# SuperCap-NEW_V2_1_2.net
KiCad netlist of a schematic drawn in Altium Designer
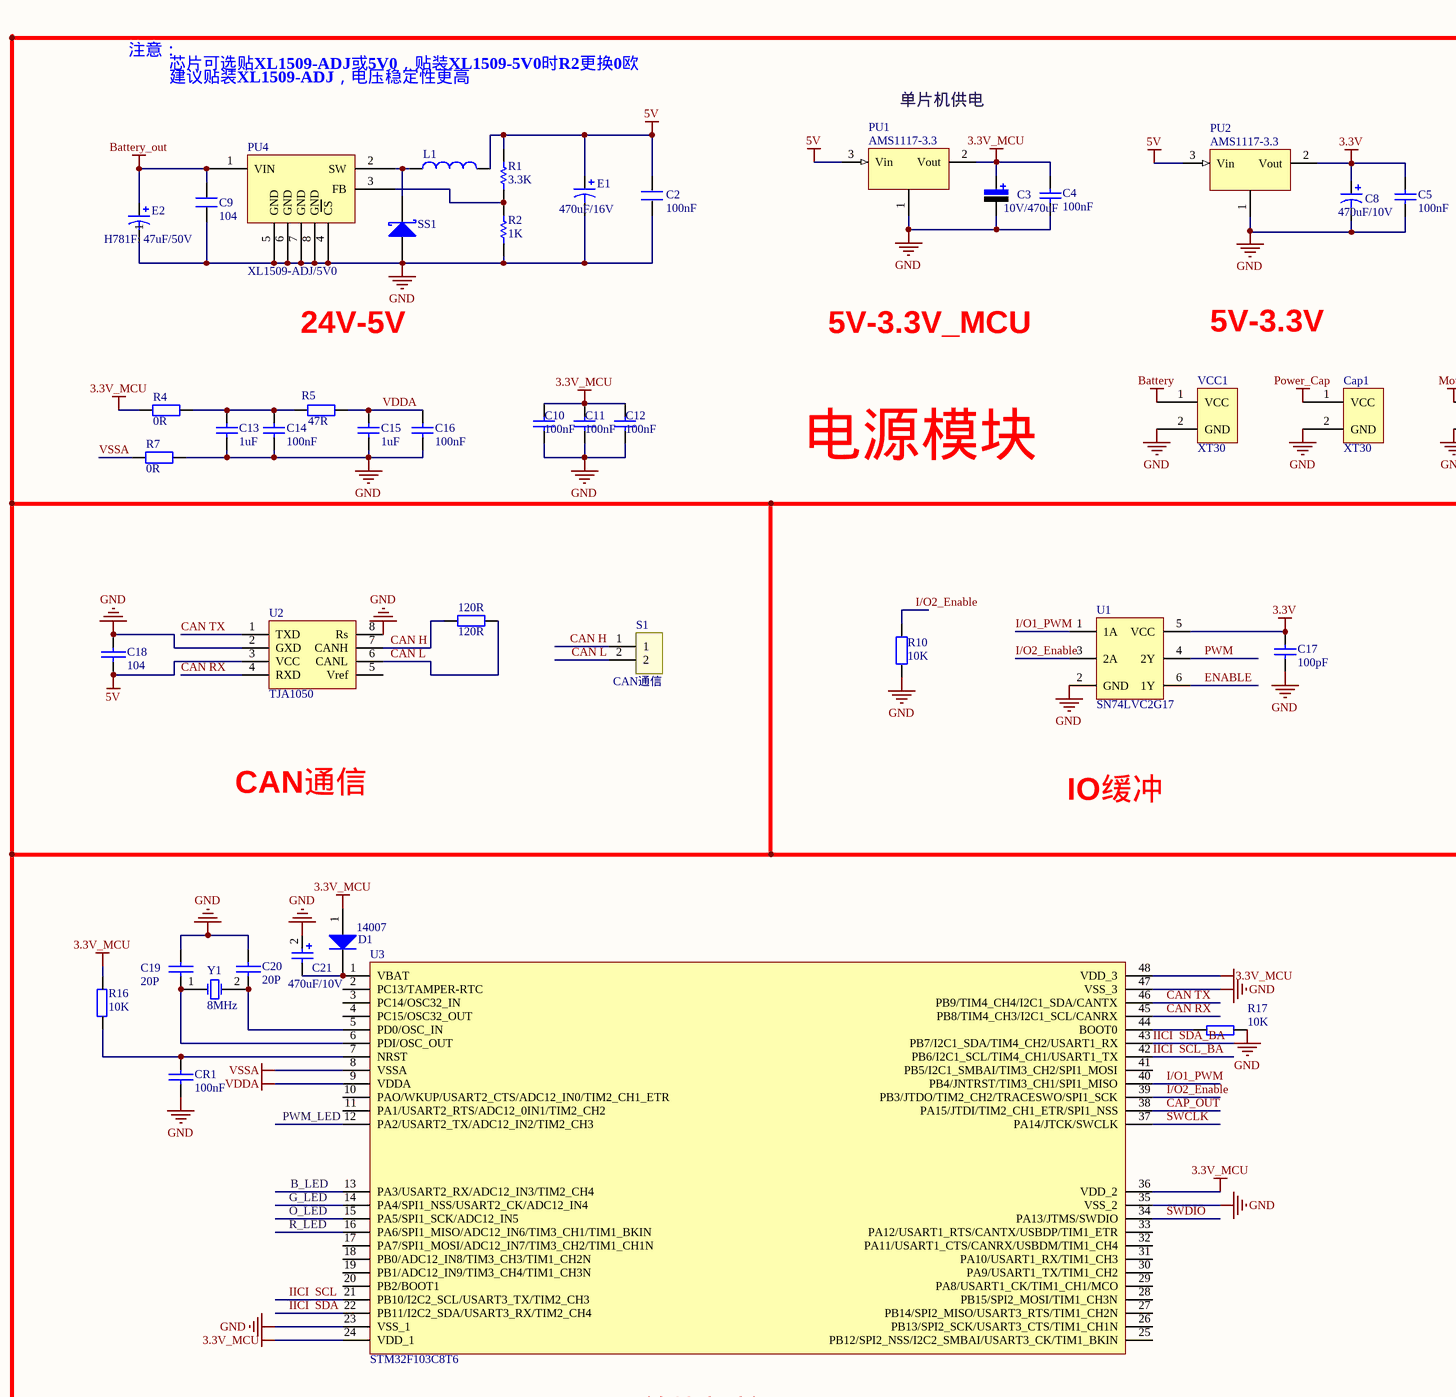
[diagram p0: SuperCap-NEW_V2.1.2.SchDoc, top left]
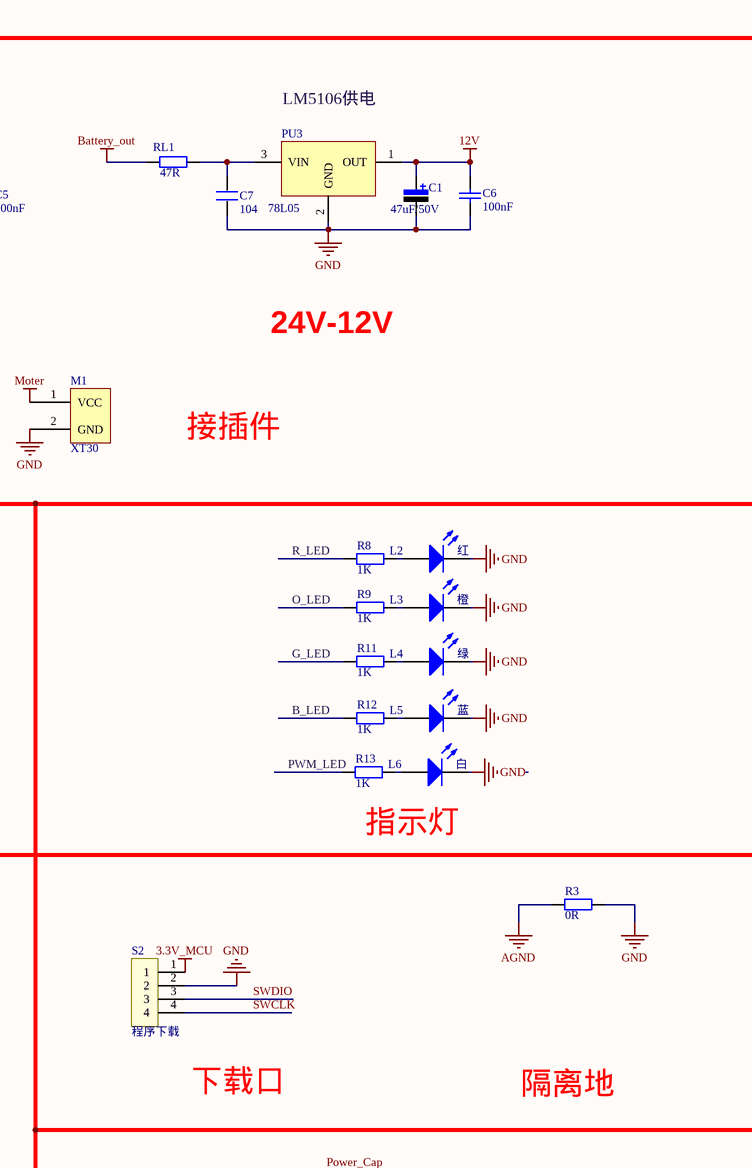
[diagram p1: SuperCap-NEW_V2.1.2.SchDoc, top right]
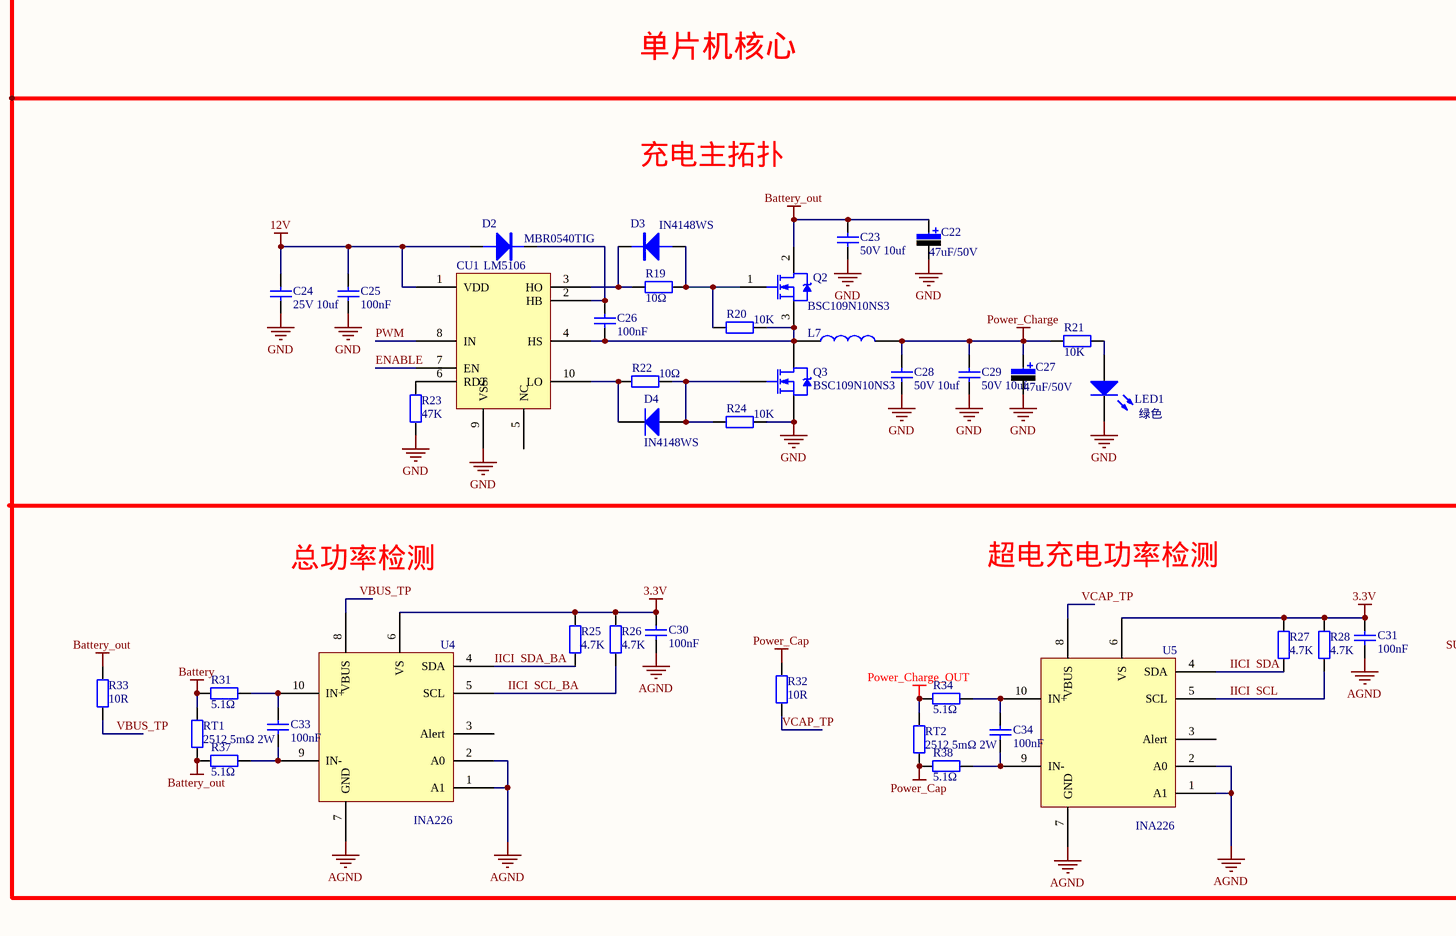
[diagram p2: SuperCap-NEW_V2.1.2.SchDoc, bottom left]
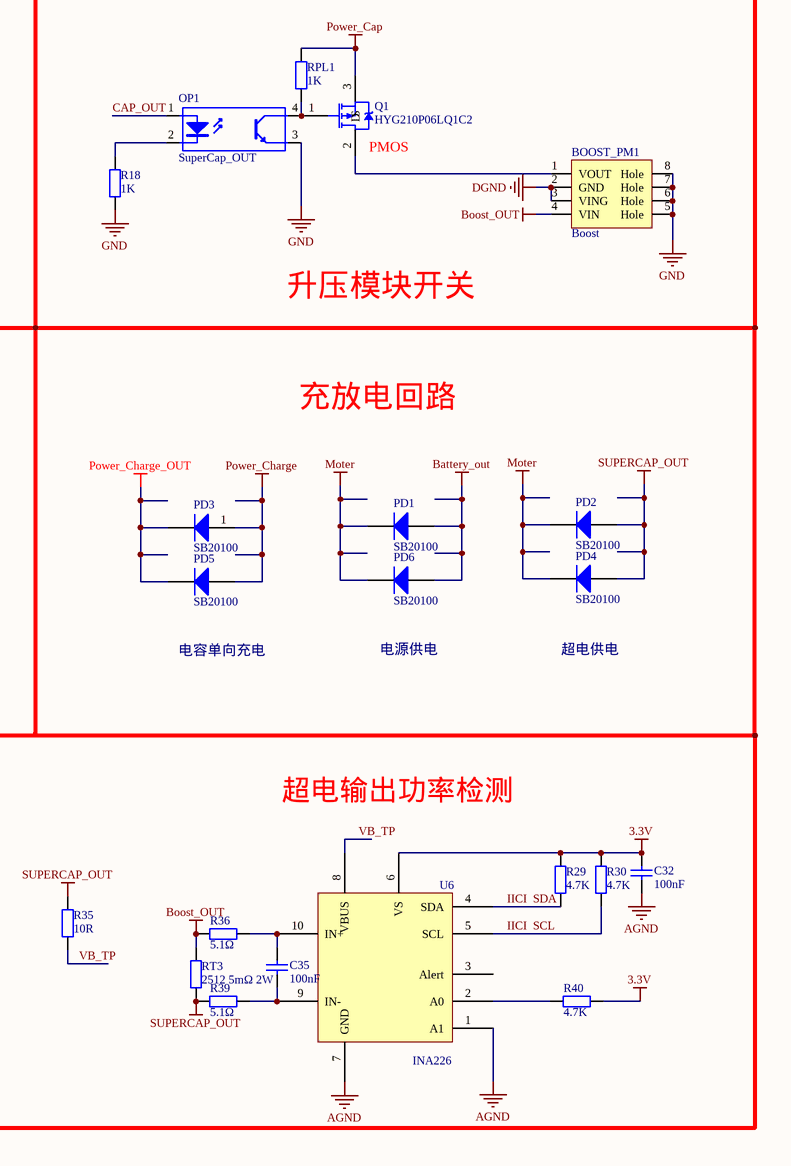
[diagram p3: SuperCap-NEW_V2.1.2.SchDoc, bottom right]

(export (version "E")
  (design (tool "Eeschema 10.0.6"))
  (components
    (comp (ref "120R")
      (value "120R")
      (footprint "0603-1")
      (description "Resistor")
      (fields (field (name "Comment") "Res2") (field (name "PUBLISHER") "Altium Limited"))
      (libsource (lib "Miscellaneous Devices") (part "Res2"))
    )
    (comp (ref "BOOST_PM1")
      (value "Boost")
      (footprint "Boost_Block")
      (libsource (lib "My package") (part "Boost"))
    )
    (comp (ref "C1")
      (value "47uF/50V")
      (footprint "CAP-SMD_BD6.3-L6.6-W6.6-FD")
      (description "极性电解电容")
      (fields (field (name "PUBLISHER") "Altium Limited"))
      (libsource (lib "Fszhang") (part "Cap Pol"))
    )
    (comp (ref "C2") (value "100nF") (footprint "0603C") (libsource (lib "南江主控 原理图库") (part "C")))
    (comp (ref "C3")
      (value "10V/470uF")
      (footprint "CAP-SMD_BD6.3-L6.6-W6.6-FD")
      (description "极性电解电容")
      (fields (field (name "PUBLISHER") "Altium Limited"))
      (libsource (lib "Fszhang") (part "Cap Pol"))
    )
    (comp (ref "C4")
      (value "100nF")
      (footprint "0603C")
      (description "无极性电容")
      (fields (field (name "PUBLISHER") "Altium Limited"))
      (libsource (lib "Fszhang") (part "Cap"))
    )
    (comp (ref "C5")
      (value "100nF")
      (footprint "0603C")
      (description "无极性电容")
      (fields (field (name "PUBLISHER") "Altium Limited"))
      (libsource (lib "Fszhang") (part "Cap"))
    )
    (comp (ref "C6")
      (value "100nF")
      (footprint "0603C")
      (description "无极性电容")
      (fields (field (name "PUBLISHER") "Altium Limited"))
      (libsource (lib "Fszhang") (part "Cap"))
    )
    (comp (ref "C7") (value "104") (footprint "0603C") (libsource (lib "103驱动2") (part "C")))
    (comp (ref "C8")
      (value "470uF/10V")
      (footprint "CAP-SMD_BD6.3-L6.6-W6.6-FD")
      (description "Polarized Capacitor (Radial)")
      (fields (field (name "Comment") "Cap Pol1") (field (name "PUBLISHER") "Altium Limited"))
      (libsource (lib "Miscellaneous Devices") (part "Cap Pol1"))
    )
    (comp (ref "C9") (value "104") (footprint "0603C") (libsource (lib "南江主控 原理图库") (part "C")))
    (comp (ref "C10")
      (value "100nF")
      (footprint "0603C")
      (description "无极性电容")
      (fields (field (name "PUBLISHER") "Altium Limited"))
      (libsource (lib "Fszhang") (part "Cap"))
    )
    (comp (ref "C11")
      (value "100nF")
      (footprint "0603C")
      (description "无极性电容")
      (fields (field (name "PUBLISHER") "Altium Limited"))
      (libsource (lib "Fszhang") (part "Cap"))
    )
    (comp (ref "C12")
      (value "100nF")
      (footprint "0603C")
      (description "无极性电容")
      (fields (field (name "PUBLISHER") "Altium Limited"))
      (libsource (lib "Fszhang") (part "Cap"))
    )
    (comp (ref "C13")
      (value "1uF")
      (footprint "0603C")
      (description "无极性电容")
      (fields (field (name "PUBLISHER") "Altium Limited"))
      (libsource (lib "Fszhang") (part "Cap"))
    )
    (comp (ref "C14")
      (value "100nF")
      (footprint "0603C")
      (description "无极性电容")
      (fields (field (name "PUBLISHER") "Altium Limited"))
      (libsource (lib "Fszhang") (part "Cap"))
    )
    (comp (ref "C15")
      (value "1uF")
      (footprint "0603C")
      (description "无极性电容")
      (fields (field (name "PUBLISHER") "Altium Limited"))
      (libsource (lib "Fszhang") (part "Cap"))
    )
    (comp (ref "C16")
      (value "100nF")
      (footprint "0603C")
      (description "无极性电容")
      (fields (field (name "PUBLISHER") "Altium Limited"))
      (libsource (lib "Fszhang") (part "Cap"))
    )
    (comp (ref "C17")
      (value "100pF")
      (footprint "0603C")
      (description "Capacitor")
      (fields (field (name "Comment") "Cap") (field (name "PUBLISHER") "Altium Limited"))
      (libsource (lib "Miscellaneous Devices") (part "Cap"))
    )
    (comp (ref "C18") (value "104") (footprint "0603C") (libsource (lib "ZBC124Schlib1") (part "CAP-1")))
    (comp (ref "C19") (value "20P") (footprint "0603C") (libsource (lib "ZBC124Schlib1") (part "CAP-1")))
    (comp (ref "C20") (value "20P") (footprint "0603C") (libsource (lib "ZBC124Schlib1") (part "CAP-1")))
    (comp (ref "C21")
      (value "470uF/10V")
      (footprint "CAP-SMD_BD6.3-L6.6-W6.6-FD")
      (description "Polarized Capacitor (Radial)")
      (fields (field (name "PUBLISHER") "Altium Limited"))
      (libsource (lib "*") (part "Cap Pol1"))
    )
    (comp (ref "C22")
      (value "47uF/50V")
      (footprint "CAP-SMD_BD8.0-L8.3-W8.3-FD")
      (description "极性电解电容")
      (fields (field (name "PUBLISHER") "Altium Limited"))
      (libsource (lib "Fszhang") (part "Cap Pol"))
    )
    (comp (ref "C23")
      (value "50V 10uf")
      (footprint "0603C")
      (description "无极性电容")
      (fields (field (name "PUBLISHER") "Altium Limited"))
      (libsource (lib "Fszhang") (part "Cap"))
    )
    (comp (ref "C24")
      (value "25V 10uf")
      (footprint "0603C")
      (description "无极性电容")
      (fields (field (name "PUBLISHER") "Altium Limited"))
      (libsource (lib "Fszhang") (part "Cap"))
    )
    (comp (ref "C25")
      (value "100nF")
      (footprint "0603C")
      (description "无极性电容")
      (fields (field (name "PUBLISHER") "Altium Limited"))
      (libsource (lib "Fszhang") (part "Cap"))
    )
    (comp (ref "C26")
      (value "100nF")
      (footprint "0603C")
      (description "无极性电容")
      (fields (field (name "PUBLISHER") "Altium Limited"))
      (libsource (lib "Fszhang") (part "Cap"))
    )
    (comp (ref "C27")
      (value "47uF/50V")
      (footprint "CAP-SMD_BD8.0-L8.3-W8.3-FD")
      (description "极性电解电容")
      (fields (field (name "PUBLISHER") "Altium Limited"))
      (libsource (lib "Fszhang") (part "Cap Pol"))
    )
    (comp (ref "C28")
      (value "50V 10uf")
      (footprint "0603C")
      (description "无极性电容")
      (fields (field (name "PUBLISHER") "Altium Limited"))
      (libsource (lib "Fszhang") (part "Cap"))
    )
    (comp (ref "C29")
      (value "50V 10uf")
      (footprint "0603C")
      (description "无极性电容")
      (fields (field (name "PUBLISHER") "Altium Limited"))
      (libsource (lib "Fszhang") (part "Cap"))
    )
    (comp (ref "C30")
      (value "100nF")
      (footprint "0603C")
      (description "无极性电容")
      (fields (field (name "PUBLISHER") "Altium Limited"))
      (libsource (lib "Fszhang") (part "Cap"))
    )
    (comp (ref "C31")
      (value "100nF")
      (footprint "0603C")
      (description "无极性电容")
      (fields (field (name "PUBLISHER") "Altium Limited"))
      (libsource (lib "Fszhang") (part "Cap"))
    )
    (comp (ref "C32")
      (value "100nF")
      (footprint "0603C")
      (description "无极性电容")
      (fields (field (name "PUBLISHER") "Altium Limited"))
      (libsource (lib "Fszhang") (part "Cap"))
    )
    (comp (ref "C33")
      (value "100nF")
      (footprint "0603C")
      (description "无极性电容")
      (fields (field (name "PUBLISHER") "Altium Limited"))
      (libsource (lib "Fszhang") (part "Cap"))
    )
    (comp (ref "C34")
      (value "100nF")
      (footprint "0603C")
      (description "无极性电容")
      (fields (field (name "PUBLISHER") "Altium Limited"))
      (libsource (lib "Fszhang") (part "Cap"))
    )
    (comp (ref "C35")
      (value "100nF")
      (footprint "0603C")
      (description "无极性电容")
      (fields (field (name "PUBLISHER") "Altium Limited"))
      (libsource (lib "Fszhang") (part "Cap"))
    )
    (comp (ref "Cap1") (value "XT30") (footprint "XT30") (libsource (lib "电源模块") (part "JP-2")))
    (comp (ref "CR1") (value "100nF") (footprint "0603C") (libsource (lib "ZBC124Schlib1") (part "CAP-1")))
    (comp (ref "CU1") (value "LM5106") (footprint "MSOP_10") (libsource (lib "Schlib3") (part "Component_1")))
    (comp (ref "D1")
      (value "14007")
      (footprint "SOD123")
      (description "High Conductance Fast Diode")
      (fields (field (name "PUBLISHER") "Altium Limited"))
      (libsource (lib "Miscellaneous Devices") (part "Diode 1N914"))
    )
    (comp (ref "D2") (value "MBR0540TIG") (footprint "SOD123") (libsource (lib "ZBC124Schlib1") (part "D-1")))
    (comp (ref "D3") (value "IN4148WS") (footprint "SOD123") (libsource (lib "ZBC124Schlib1") (part "D-1")))
    (comp (ref "D4")
      (value "IN4148WS")
      (footprint "SOD123")
      (description "High Conductance Fast Diode")
      (fields (field (name "PUBLISHER") "Altium Limited"))
      (libsource (lib "") (part "Diode 1N914_1"))
    )
    (comp (ref "E1")
      (value "470uF/16V")
      (footprint "CAP-SMD_BD8.0-L8.3-W8.3-FD")
      (description "Polarized Capacitor (Radial)")
      (fields (field (name "Comment") "Cap Pol1") (field (name "PUBLISHER") "Altium Limited"))
      (libsource (lib "Miscellaneous Devices") (part "Cap Pol1"))
    )
    (comp (ref "E2")
      (value "Cap Pol1")
      (footprint "CAP-SMD_BD8.0-L8.3-W8.3-FD")
      (description "Polarized Capacitor (Radial)")
      (fields (field (name "H781F") "47uF/50V") (field (name "PUBLISHER") "Altium Limited"))
      (libsource (lib "") (part "Cap Pol1_1"))
    )
    (comp (ref "L1")
      (value "Inductor")
      (footprint "L 6*6")
      (fields (field (name "PUBLISHER") "Altium Limited"))
      (libsource (lib "Miscellaneous Devices") (part "Inductor"))
    )
    (comp (ref "L2")
      (value "红")
      (footprint "LED_0805")
      (description "发光二极管")
      (fields (field (name "PUBLISHER") "Altium Limited"))
      (libsource (lib "Fszhang") (part "LED0"))
    )
    (comp (ref "L3")
      (value "橙")
      (footprint "LED_0805")
      (description "发光二极管")
      (fields (field (name "PUBLISHER") "Altium Limited"))
      (libsource (lib "Fszhang") (part "LED0"))
    )
    (comp (ref "L4")
      (value "绿")
      (footprint "LED_0805")
      (description "发光二极管")
      (fields (field (name "PUBLISHER") "Altium Limited"))
      (libsource (lib "Fszhang") (part "LED0"))
    )
    (comp (ref "L5")
      (value "蓝")
      (footprint "LED_0805")
      (description "发光二极管")
      (fields (field (name "PUBLISHER") "Altium Limited"))
      (libsource (lib "Fszhang") (part "LED0"))
    )
    (comp (ref "L6")
      (value "白")
      (footprint "LED_0805")
      (description "发光二极管")
      (fields (field (name "PUBLISHER") "Altium Limited"))
      (libsource (lib "Fszhang") (part "LED0"))
    )
    (comp (ref "L7")
      (value "68UH")
      (footprint "IND-TH_L14.0-W6.5-P8.00-D0.6")
      (libsource (lib "103驱动2") (part "Inductance"))
    )
    (comp (ref "LED1")
      (value "绿色")
      (footprint "LED_0805")
      (description "发光二极管")
      (fields (field (name "PUBLISHER") "Altium Limited"))
      (libsource (lib "Fszhang") (part "LED0"))
    )
    (comp (ref "M1") (value "XT30") (footprint "XT30") (libsource (lib "电源模块") (part "JP-2")))
    (comp (ref "OP1")
      (value "SuperCap_OUT")
      (footprint "SOP-4_L6.5-W4.6-P2.54-LS10.2-TL")
      (description "4-Pin Phototransistor Optocoupler")
      (fields (field (name "PUBLISHER") "Altium Limited"))
      (libsource (lib "Miscellaneous Devices") (part "Optoisolator1"))
    )
    (comp (ref "PD1")
      (value "SB20100")
      (footprint "TO-277_3P-L5.4-W4.0-LS6.5-TR")
      (description "High Conductance Fast Diode")
      (fields (field (name "PUBLISHER") "Altium Limited"))
      (libsource (lib "") (part "Diode 1N914_1"))
    )
    (comp (ref "PD2")
      (value "SB20100")
      (footprint "TO-277_3P-L5.4-W4.0-LS6.5-TR")
      (description "High Conductance Fast Diode")
      (fields (field (name "PUBLISHER") "Altium Limited"))
      (libsource (lib "") (part "Diode 1N914_1"))
    )
    (comp (ref "PD3")
      (value "SB20100")
      (footprint "TO-277_3P-L5.4-W4.0-LS6.5-TR")
      (description "High Conductance Fast Diode")
      (fields (field (name "PUBLISHER") "Altium Limited"))
      (libsource (lib "Miscellaneous Devices") (part "Diode 1N914"))
    )
    (comp (ref "PD4")
      (value "SB20100")
      (footprint "TO-277_3P-L5.4-W4.0-LS6.5-TR")
      (description "High Conductance Fast Diode")
      (fields (field (name "PUBLISHER") "Altium Limited"))
      (libsource (lib "") (part "Diode 1N914_1"))
    )
    (comp (ref "PD5")
      (value "SB20100")
      (footprint "TO-277_3P-L5.4-W4.0-LS6.5-TR")
      (description "High Conductance Fast Diode")
      (fields (field (name "PUBLISHER") "Altium Limited"))
      (libsource (lib "") (part "Diode 1N914_1"))
    )
    (comp (ref "PD6")
      (value "SB20100")
      (footprint "TO-277_3P-L5.4-W4.0-LS6.5-TR")
      (description "High Conductance Fast Diode")
      (fields (field (name "PUBLISHER") "Altium Limited"))
      (libsource (lib "") (part "Diode 1N914_1"))
    )
    (comp (ref "PU1") (value "AMS1117-3.3") (footprint "SOT-223") (libsource (lib "*") (part "LD1117")))
    (comp (ref "PU2") (value "AMS1117-3.3") (footprint "SOT-223") (libsource (lib "*") (part "LD1117")))
    (comp (ref "PU3")
      (value "78L05")
      (footprint "SOT-89-3_L4.5-W2.5-P1.50-LS4.2-BR")
      (libsource (lib "My package") (part "78L05"))
    )
    (comp (ref "PU4")
      (value "XL1509-ADJ/5V0")
      (footprint "SOP8 N")
      (libsource (lib "电源转接板") (part "XL1509-ADJ"))
    )
    (comp (ref "Q1")
      (value "HYG210P06LQ1C2")
      (footprint "MOS_PQFN")
      (description "P-Channel Power MOSFET")
      (fields (field (name "PUBLISHER") "Altium Limited"))
      (libsource (lib "Miscellaneous Devices") (part "PMOS-2"))
    )
    (comp (ref "Q2")
      (value "BSC109N10NS3")
      (footprint "PDFN-8_L4.9-W5.8-P1.27-LS6.1-BL_2")
      (description "N-Channel Power MOSFET")
      (fields (field (name "PUBLISHER") "Altium Limited"))
      (libsource (lib "Miscellaneous Devices") (part "NMOS-2"))
    )
    (comp (ref "Q3")
      (value "BSC109N10NS3")
      (footprint "PDFN-8_L4.9-W5.8-P1.27-LS6.1-BL_2")
      (description "N-Channel Power MOSFET")
      (fields (field (name "PUBLISHER") "Altium Limited"))
      (libsource (lib "") (part "NMOS-2_1"))
    )
    (comp (ref "R1")
      (value "3.3K")
      (footprint "R0603")
      (description "Resistor")
      (fields (field (name "Comment") "Res1") (field (name "PUBLISHER") "Altium Limited"))
      (libsource (lib "Miscellaneous Devices") (part "Res1"))
    )
    (comp (ref "R2")
      (value "1K")
      (footprint "R0603")
      (description "Resistor")
      (fields (field (name "Comment") "Res1") (field (name "PUBLISHER") "Altium Limited"))
      (libsource (lib "Miscellaneous Devices") (part "Res1"))
    )
    (comp (ref "R3")
      (value "0R")
      (footprint "0603-1")
      (description "Resistor")
      (fields (field (name "Comment") "Res2") (field (name "PUBLISHER") "Altium Limited"))
      (libsource (lib "Miscellaneous Devices") (part "Res2"))
    )
    (comp (ref "R4")
      (value "0R")
      (footprint "0603-1")
      (description "贴片电阻")
      (fields (field (name "PUBLISHER") "Altium Limited"))
      (libsource (lib "") (part "Res1_1"))
    )
    (comp (ref "R5")
      (value "47R")
      (footprint "0603-1")
      (description "贴片电阻")
      (fields (field (name "PUBLISHER") "Altium Limited"))
      (libsource (lib "") (part "Res1_1"))
    )
    (comp (ref "R7")
      (value "0R")
      (footprint "0603-1")
      (description "贴片电阻")
      (fields (field (name "PUBLISHER") "Altium Limited"))
      (libsource (lib "") (part "Res1_1"))
    )
    (comp (ref "R8")
      (value "1K")
      (footprint "0603-1")
      (description "Resistor")
      (fields (field (name "Comment") "Res2") (field (name "PUBLISHER") "Altium Limited"))
      (libsource (lib "Miscellaneous Devices") (part "Res2"))
    )
    (comp (ref "R9")
      (value "1K")
      (footprint "0603-1")
      (description "Resistor")
      (fields (field (name "Comment") "Res2") (field (name "PUBLISHER") "Altium Limited"))
      (libsource (lib "") (part "Res2_1"))
    )
    (comp (ref "R10")
      (value "10K")
      (footprint "0603-1")
      (description "Resistor")
      (fields (field (name "Comment") "Res2") (field (name "PUBLISHER") "Altium Limited"))
      (libsource (lib "") (part "Res2_2"))
    )
    (comp (ref "R11")
      (value "1K")
      (footprint "0603-1")
      (description "Resistor")
      (fields (field (name "Comment") "Res2") (field (name "PUBLISHER") "Altium Limited"))
      (libsource (lib "") (part "Res2_1"))
    )
    (comp (ref "R12")
      (value "1K")
      (footprint "0603-1")
      (description "Resistor")
      (fields (field (name "Comment") "Res2") (field (name "PUBLISHER") "Altium Limited"))
      (libsource (lib "") (part "Res2_1"))
    )
    (comp (ref "R13")
      (value "1K")
      (footprint "0603-1")
      (description "Resistor")
      (fields (field (name "Comment") "Res2") (field (name "PUBLISHER") "Altium Limited"))
      (libsource (lib "") (part "Res2_1"))
    )
    (comp (ref "R16") (value "10K") (footprint "0603-1") (libsource (lib "WARSHIP") (part "R")))
    (comp (ref "R17") (value "10K") (footprint "0603-1") (libsource (lib "WARSHIP") (part "R")))
    (comp (ref "R18")
      (value "1K")
      (footprint "0603-1")
      (description "贴片电阻")
      (fields (field (name "PUBLISHER") "Altium Limited"))
      (libsource (lib "Fszhang") (part "Res1"))
    )
    (comp (ref "R19")
      (value "10Ω")
      (footprint "0603-1")
      (description "贴片电阻")
      (fields (field (name "PUBLISHER") "Altium Limited"))
      (libsource (lib "") (part "Res1_1"))
    )
    (comp (ref "R20")
      (value "10K")
      (footprint "0603-1")
      (description "贴片电阻")
      (fields (field (name "PUBLISHER") "Altium Limited"))
      (libsource (lib "") (part "Res1_1"))
    )
    (comp (ref "R21")
      (value "10K")
      (footprint "0603-1")
      (description "贴片电阻")
      (fields (field (name "PUBLISHER") "Altium Limited"))
      (libsource (lib "") (part "Res1_2"))
    )
    (comp (ref "R22")
      (value "10Ω")
      (footprint "0603-1")
      (description "贴片电阻")
      (fields (field (name "PUBLISHER") "Altium Limited"))
      (libsource (lib "") (part "Res1_1"))
    )
    (comp (ref "R23")
      (value "47K")
      (footprint "0603-1")
      (description "贴片电阻")
      (fields (field (name "PUBLISHER") "Altium Limited"))
      (libsource (lib "Fszhang") (part "Res1"))
    )
    (comp (ref "R24")
      (value "10K")
      (footprint "0603-1")
      (description "贴片电阻")
      (fields (field (name "PUBLISHER") "Altium Limited"))
      (libsource (lib "") (part "Res1_1"))
    )
    (comp (ref "R25")
      (value "4.7K")
      (footprint "0603-1")
      (description "贴片电阻")
      (fields (field (name "PUBLISHER") "Altium Limited"))
      (libsource (lib "Fszhang") (part "Res1"))
    )
    (comp (ref "R26")
      (value "4.7K")
      (footprint "0603-1")
      (description "贴片电阻")
      (fields (field (name "PUBLISHER") "Altium Limited"))
      (libsource (lib "Fszhang") (part "Res1"))
    )
    (comp (ref "R27")
      (value "4.7K")
      (footprint "0603-1")
      (description "贴片电阻")
      (fields (field (name "PUBLISHER") "Altium Limited"))
      (libsource (lib "Fszhang") (part "Res1"))
    )
    (comp (ref "R28")
      (value "4.7K")
      (footprint "0603-1")
      (description "贴片电阻")
      (fields (field (name "PUBLISHER") "Altium Limited"))
      (libsource (lib "Fszhang") (part "Res1"))
    )
    (comp (ref "R29")
      (value "4.7K")
      (footprint "0603-1")
      (description "贴片电阻")
      (fields (field (name "PUBLISHER") "Altium Limited"))
      (libsource (lib "Fszhang") (part "Res1"))
    )
    (comp (ref "R30")
      (value "4.7K")
      (footprint "0603-1")
      (description "贴片电阻")
      (fields (field (name "PUBLISHER") "Altium Limited"))
      (libsource (lib "Fszhang") (part "Res1"))
    )
    (comp (ref "R31")
      (value "5.1Ω")
      (footprint "0603-1")
      (description "贴片电阻")
      (fields (field (name "PUBLISHER") "Altium Limited"))
      (libsource (lib "") (part "Res1_2"))
    )
    (comp (ref "R32")
      (value "10R")
      (footprint "0603-1")
      (description "Resistor")
      (fields (field (name "Comment") "Res2") (field (name "PUBLISHER") "Altium Limited"))
      (libsource (lib "") (part "Res2_2"))
    )
    (comp (ref "R33")
      (value "10R")
      (footprint "0603-1")
      (description "Resistor")
      (fields (field (name "Comment") "Res2") (field (name "PUBLISHER") "Altium Limited"))
      (libsource (lib "") (part "Res2_2"))
    )
    (comp (ref "R34")
      (value "5.1Ω")
      (footprint "0603-1")
      (description "贴片电阻")
      (fields (field (name "PUBLISHER") "Altium Limited"))
      (libsource (lib "") (part "Res1_2"))
    )
    (comp (ref "R35")
      (value "10R")
      (footprint "0603-1")
      (description "Resistor")
      (fields (field (name "Comment") "Res2") (field (name "PUBLISHER") "Altium Limited"))
      (libsource (lib "") (part "Res2_2"))
    )
    (comp (ref "R36")
      (value "5.1Ω")
      (footprint "0603-1")
      (description "贴片电阻")
      (fields (field (name "PUBLISHER") "Altium Limited"))
      (libsource (lib "") (part "Res1_2"))
    )
    (comp (ref "R37")
      (value "5.1Ω")
      (footprint "0603-1")
      (description "贴片电阻")
      (fields (field (name "PUBLISHER") "Altium Limited"))
      (libsource (lib "") (part "Res1_2"))
    )
    (comp (ref "R38")
      (value "5.1Ω")
      (footprint "0603-1")
      (description "贴片电阻")
      (fields (field (name "PUBLISHER") "Altium Limited"))
      (libsource (lib "") (part "Res1_2"))
    )
    (comp (ref "R39")
      (value "5.1Ω")
      (footprint "0603-1")
      (description "贴片电阻")
      (fields (field (name "PUBLISHER") "Altium Limited"))
      (libsource (lib "") (part "Res1_2"))
    )
    (comp (ref "R40")
      (value "4.7K")
      (footprint "0603-1")
      (description "Resistor")
      (fields (field (name "Comment") "Res2") (field (name "PUBLISHER") "Altium Limited"))
      (libsource (lib "Miscellaneous Devices") (part "Res2"))
    )
    (comp (ref "RL1")
      (value "47R")
      (footprint "0603-1")
      (description "贴片电阻")
      (fields (field (name "PUBLISHER") "Altium Limited"))
      (libsource (lib "") (part "Res1_1"))
    )
    (comp (ref "RPL1")
      (value "1K")
      (footprint "0603-1")
      (description "贴片电阻")
      (fields (field (name "PUBLISHER") "Altium Limited"))
      (libsource (lib "Fszhang") (part "Res1"))
    )
    (comp (ref "RT1")
      (value "2512 5mΩ 2W")
      (footprint "FUSE-SMD_L6.1-W2.7 - duplicate")
      (description "贴片电阻")
      (fields (field (name "PUBLISHER") "Altium Limited"))
      (libsource (lib "Fszhang") (part "Res1"))
    )
    (comp (ref "RT2")
      (value "2512 5mΩ 2W")
      (footprint "FUSE-SMD_L6.1-W2.7 - duplicate")
      (description "贴片电阻")
      (fields (field (name "PUBLISHER") "Altium Limited"))
      (libsource (lib "Fszhang") (part "Res1"))
    )
    (comp (ref "RT3")
      (value "2512 5mΩ 2W")
      (footprint "FUSE-SMD_L6.1-W2.7 - duplicate")
      (description "贴片电阻")
      (fields (field (name "PUBLISHER") "Altium Limited"))
      (libsource (lib "Fszhang") (part "Res1"))
    )
    (comp (ref "S1") (value "CAN通信") (footprint "1.25_2Pin") (libsource (lib "ZBC123Schlib1") (part "S-2")))
    (comp (ref "S2") (value "程序下载") (footprint "S-4") (libsource (lib "ZBC123Schlib1") (part "S-4")))
    (comp (ref "SS1")
      (value "D Schottky")
      (footprint "贴片M7")
      (description "Schottky Diode")
      (fields (field (name "PUBLISHER") "Altium Limited"))
      (libsource (lib "Miscellaneous Devices") (part "D Schottky"))
    )
    (comp (ref "U1")
      (value "SN74LVC2G17")
      (footprint "SOT-23-6_L2.9-W1.6-P0.95-LS2.8-BR")
      (libsource (lib "My package") (part "SN74LVC2G17"))
    )
    (comp (ref "U2") (value "TJA1050") (footprint "SOP8 N") (libsource (lib "底盘主控") (part "24C02")))
    (comp (ref "U3")
      (value "STM32F103C8T6")
      (footprint "LQFP-48_M")
      (libsource (lib "WARSHIP") (part "STM32F103C8T6"))
    )
    (comp (ref "U4") (value "INA226") (footprint "MSOP_10") (libsource (lib "Schlib4") (part "Component_1")))
    (comp (ref "U5") (value "INA226") (footprint "MSOP_10") (libsource (lib "Schlib4") (part "Component_1")))
    (comp (ref "U6") (value "INA226") (footprint "MSOP_10") (libsource (lib "Schlib4") (part "Component_1")))
    (comp (ref "VCC1") (value "XT30") (footprint "XT30") (libsource (lib "电源模块") (part "JP-2")))
    (comp (ref "Y1")
      (value "8MHz")
      (footprint "X-SM49")
      (description "Crystal Oscillator")
      (fields (field (name "PUBLISHER") "Altium Limited"))
      (libsource (lib "WARSHIP") (part "XTAL"))
    )
  )
  (nets
    (net (code "2") (name "/B_LED") (class "Default")
      (node (ref "R12") (pin "2") (pinfunction "2_2") (pintype "passive"))
      (node (ref "U3") (pin "13") (pinfunction "PA3/USART2_RX/ADC12_IN3/TIM2_CH4_13") (pintype "passive"))
    )
    (net (code "3") (name "/CAN H") (class "Default")
      (node (ref "120R") (pin "1") (pinfunction "1_1") (pintype "passive"))
      (node (ref "S1") (pin "1") (pinfunction "1_1") (pintype "passive"))
      (node (ref "U2") (pin "7") (pinfunction "CANH_7") (pintype "passive"))
    )
    (net (code "4") (name "/CAN L") (class "Default")
      (node (ref "120R") (pin "2") (pinfunction "2_2") (pintype "passive"))
      (node (ref "S1") (pin "2") (pinfunction "2_2") (pintype "passive"))
      (node (ref "U2") (pin "6") (pinfunction "CANL_6") (pintype "passive"))
    )
    (net (code "5") (name "/CAN RX") (class "Default")
      (node (ref "U2") (pin "4") (pinfunction "RXD_4") (pintype "passive"))
      (node (ref "U3") (pin "45") (pinfunction "PB8/TIM4_CH3/I2C1_SCL/CANRX_45") (pintype "passive"))
    )
    (net (code "6") (name "/CAN TX") (class "Default")
      (node (ref "U2") (pin "1") (pinfunction "TXD_1") (pintype "passive"))
      (node (ref "U3") (pin "46") (pinfunction "PB9/TIM4_CH4/I2C1_SDA/CANTX_46") (pintype "passive"))
    )
    (net (code "7") (name "/CAP_OUT") (class "Default")
      (node (ref "OP1") (pin "1") (pinfunction "A_1") (pintype "passive"))
      (node (ref "U3") (pin "38") (pinfunction "PA15/JTDI/TIM2_CH1_ETR/SPI1_NSS_38") (pintype "passive"))
    )
    (net (code "8") (name "/ENABLE") (class "Default")
      (node (ref "CU1") (pin "7") (pinfunction "EN_7") (pintype "passive"))
      (node (ref "U1") (pin "6") (pinfunction "1Y_6") (pintype "passive"))
    )
    (net (code "9") (name "/G_LED") (class "Default")
      (node (ref "R11") (pin "2") (pinfunction "2_2") (pintype "passive"))
      (node (ref "U3") (pin "14") (pinfunction "PA4/SPI1_NSS/USART2_CK/ADC12_IN4_14") (pintype "passive"))
    )
    (net (code "10") (name "/IICI  SCL") (class "Default")
      (node (ref "R28") (pin "2") (pinfunction "2_2") (pintype "passive"))
      (node (ref "R30") (pin "2") (pinfunction "2_2") (pintype "passive"))
      (node (ref "U3") (pin "21") (pinfunction "PB10/I2C2_SCL/USART3_TX/TIM2_CH3_21") (pintype "passive"))
      (node (ref "U5") (pin "5") (pinfunction "SCL_5") (pintype "passive"))
      (node (ref "U6") (pin "5") (pinfunction "SCL_5") (pintype "passive"))
    )
    (net (code "11") (name "/IICI  SCL_BA") (class "Default")
      (node (ref "R26") (pin "2") (pinfunction "2_2") (pintype "passive"))
      (node (ref "U3") (pin "42") (pinfunction "PB6/I2C1_SCL/TIM4_CH1/USART1_TX_42") (pintype "passive"))
      (node (ref "U4") (pin "5") (pinfunction "SCL_5") (pintype "passive"))
    )
    (net (code "12") (name "/IICI  SDA") (class "Default")
      (node (ref "R27") (pin "2") (pinfunction "2_2") (pintype "passive"))
      (node (ref "R29") (pin "2") (pinfunction "2_2") (pintype "passive"))
      (node (ref "U3") (pin "22") (pinfunction "PB11/I2C2_SDA/USART3_RX/TIM2_CH4_22") (pintype "passive"))
      (node (ref "U5") (pin "4") (pinfunction "SDA_4") (pintype "passive"))
      (node (ref "U6") (pin "4") (pinfunction "SDA_4") (pintype "passive"))
    )
    (net (code "13") (name "/IICI  SDA_BA") (class "Default")
      (node (ref "R25") (pin "2") (pinfunction "2_2") (pintype "passive"))
      (node (ref "U3") (pin "43") (pinfunction "PB7/I2C1_SDA/TIM4_CH2/USART1_RX_43") (pintype "passive"))
      (node (ref "U4") (pin "4") (pinfunction "SDA_4") (pintype "passive"))
    )
    (net (code "14") (name "/I{slash}O1_PWM") (class "Default")
      (node (ref "U1") (pin "1") (pinfunction "1A_1") (pintype "passive"))
      (node (ref "U3") (pin "40") (pinfunction "PB4/JNTRST/TIM3_CH1/SPI1_MISO_40") (pintype "passive"))
    )
    (net (code "15") (name "/I{slash}O2_Enable") (class "Default")
      (node (ref "R10") (pin "1") (pinfunction "1_1") (pintype "passive"))
      (node (ref "U1") (pin "3") (pinfunction "2A_3") (pintype "passive"))
      (node (ref "U3") (pin "39") (pinfunction "PB3/JTDO/TIM2_CH2/TRACESWO/SPI1_SCK_39") (pintype "passive"))
    )
    (net (code "17") (name "/O_LED") (class "Default")
      (node (ref "R9") (pin "2") (pinfunction "2_2") (pintype "passive"))
      (node (ref "U3") (pin "15") (pinfunction "PA5/SPI1_SCK/ADC12_IN5_15") (pintype "passive"))
    )
    (net (code "18") (name "/PWM") (class "Default")
      (node (ref "CU1") (pin "8") (pinfunction "IN_8") (pintype "passive"))
      (node (ref "U1") (pin "4") (pinfunction "2Y_4") (pintype "passive"))
    )
    (net (code "19") (name "/PWM_LED") (class "Default")
      (node (ref "R13") (pin "2") (pinfunction "2_2") (pintype "passive"))
      (node (ref "U3") (pin "12") (pinfunction "PA2/USART2_TX/ADC12_IN2/TIM2_CH3_12") (pintype "passive"))
    )
    (net (code "20") (name "/R_LED") (class "Default")
      (node (ref "R8") (pin "1") (pinfunction "1_1") (pintype "passive"))
      (node (ref "U3") (pin "16") (pinfunction "PA6/SPI1_MISO/ADC12_IN6/TIM3_CH1/TIM1_BKIN_16") (pintype "passive"))
    )
    (net (code "21") (name "/SWCLK") (class "Default")
      (node (ref "S2") (pin "4") (pinfunction "4_4") (pintype "passive"))
      (node (ref "U3") (pin "37") (pinfunction "PA14/JTCK/SWCLK_37") (pintype "passive"))
    )
    (net (code "22") (name "/SWDIO") (class "Default")
      (node (ref "S2") (pin "3") (pinfunction "3_3") (pintype "passive"))
      (node (ref "U3") (pin "34") (pinfunction "PA13/JTMS/SWDIO_34") (pintype "passive"))
    )
    (net (code "23") (name "/VBUS_TP") (class "Default")
      (node (ref "R33") (pin "2") (pinfunction "2_2") (pintype "passive"))
      (node (ref "U4") (pin "8") (pinfunction "VBUS_8") (pintype "passive"))
    )
    (net (code "24") (name "/VB_TP") (class "Default")
      (node (ref "R35") (pin "2") (pinfunction "2_2") (pintype "passive"))
      (node (ref "U6") (pin "8") (pinfunction "VBUS_8") (pintype "passive"))
    )
    (net (code "25") (name "/VCAP_TP") (class "Default")
      (node (ref "R32") (pin "2") (pinfunction "2_2") (pintype "passive"))
      (node (ref "U5") (pin "8") (pinfunction "VBUS_8") (pintype "passive"))
    )
    (net (code "27") (name "3.3V") (class "Default")
      (node (ref "C17") (pin "2") (pinfunction "2_2") (pintype "passive"))
      (node (ref "C30") (pin "1") (pinfunction "1_1") (pintype "passive"))
      (node (ref "C31") (pin "1") (pinfunction "1_1") (pintype "passive"))
      (node (ref "C32") (pin "1") (pinfunction "1_1") (pintype "passive"))
      (node (ref "C5") (pin "1") (pinfunction "1_1") (pintype "passive"))
      (node (ref "C8") (pin "1") (pinfunction "1_1") (pintype "passive"))
      (node (ref "PU2") (pin "2") (pinfunction "Vout_2") (pintype "power_in"))
      (node (ref "R25") (pin "1") (pinfunction "1_1") (pintype "passive"))
      (node (ref "R26") (pin "1") (pinfunction "1_1") (pintype "passive"))
      (node (ref "R27") (pin "1") (pinfunction "1_1") (pintype "passive"))
      (node (ref "R28") (pin "1") (pinfunction "1_1") (pintype "passive"))
      (node (ref "R29") (pin "1") (pinfunction "1_1") (pintype "passive"))
      (node (ref "R30") (pin "1") (pinfunction "1_1") (pintype "passive"))
      (node (ref "R40") (pin "2") (pinfunction "2_2") (pintype "passive"))
      (node (ref "U1") (pin "5") (pinfunction "VCC_5") (pintype "passive"))
      (node (ref "U4") (pin "6") (pinfunction "VS_6") (pintype "passive"))
      (node (ref "U5") (pin "6") (pinfunction "VS_6") (pintype "passive"))
      (node (ref "U6") (pin "6") (pinfunction "VS_6") (pintype "passive"))
    )
    (net (code "28") (name "3.3V_MCU") (class "Default")
      (node (ref "C10") (pin "1") (pinfunction "1_1") (pintype "passive"))
      (node (ref "C11") (pin "1") (pinfunction "1_1") (pintype "passive"))
      (node (ref "C12") (pin "1") (pinfunction "1_1") (pintype "passive"))
      (node (ref "C3") (pin "1") (pinfunction "1_1") (pintype "passive"))
      (node (ref "C4") (pin "1") (pinfunction "1_1") (pintype "passive"))
      (node (ref "D1") (pin "1") (pinfunction "A_1") (pintype "passive"))
      (node (ref "PU1") (pin "2") (pinfunction "Vout_2") (pintype "power_in"))
      (node (ref "R16") (pin "1") (pintype "passive"))
      (node (ref "R4") (pin "1") (pinfunction "1_1") (pintype "passive"))
      (node (ref "S2") (pin "1") (pinfunction "1_1") (pintype "passive"))
      (node (ref "U3") (pin "24") (pinfunction "VDD_1_24") (pintype "passive"))
      (node (ref "U3") (pin "36") (pinfunction "VDD_2_36") (pintype "passive"))
      (node (ref "U3") (pin "48") (pinfunction "VDD_3_48") (pintype "passive"))
    )
    (net (code "29") (name "5V") (class "Default")
      (node (ref "C18") (pin "2") (pinfunction "2_2") (pintype "passive"))
      (node (ref "C2") (pin "2") (pintype "passive"))
      (node (ref "E1") (pin "1") (pinfunction "1_1") (pintype "passive"))
      (node (ref "L1") (pin "2") (pinfunction "2_2") (pintype "passive"))
      (node (ref "PU1") (pin "3") (pinfunction "Vin_3") (pintype "input"))
      (node (ref "PU2") (pin "3") (pinfunction "Vin_3") (pintype "input"))
      (node (ref "R1") (pin "2") (pinfunction "2_2") (pintype "passive"))
      (node (ref "U2") (pin "3") (pinfunction "VCC_3") (pintype "passive"))
    )
    (net (code "30") (name "12V") (class "Default")
      (node (ref "C1") (pin "1") (pinfunction "1_1") (pintype "passive"))
      (node (ref "C24") (pin "1") (pinfunction "1_1") (pintype "passive"))
      (node (ref "C25") (pin "1") (pinfunction "1_1") (pintype "passive"))
      (node (ref "C6") (pin "1") (pinfunction "1_1") (pintype "passive"))
      (node (ref "CU1") (pin "1") (pinfunction "VDD_1") (pintype "passive"))
      (node (ref "D2") (pin "1") (pinfunction "1_1") (pintype "passive"))
      (node (ref "PU3") (pin "1") (pinfunction "OUT_1") (pintype "passive"))
    )
    (net (code "31") (name "AGND") (class "Default")
      (node (ref "C30") (pin "2") (pinfunction "2_2") (pintype "passive"))
      (node (ref "C31") (pin "2") (pinfunction "2_2") (pintype "passive"))
      (node (ref "C32") (pin "2") (pinfunction "2_2") (pintype "passive"))
      (node (ref "R3") (pin "1") (pinfunction "1_1") (pintype "passive"))
      (node (ref "U4") (pin "1") (pinfunction "A1_1") (pintype "passive"))
      (node (ref "U4") (pin "2") (pinfunction "A0_2") (pintype "passive"))
      (node (ref "U4") (pin "7") (pinfunction "GND_7") (pintype "passive"))
      (node (ref "U5") (pin "1") (pinfunction "A1_1") (pintype "passive"))
      (node (ref "U5") (pin "2") (pinfunction "A0_2") (pintype "passive"))
      (node (ref "U5") (pin "7") (pinfunction "GND_7") (pintype "passive"))
      (node (ref "U6") (pin "1") (pinfunction "A1_1") (pintype "passive"))
      (node (ref "U6") (pin "7") (pinfunction "GND_7") (pintype "passive"))
    )
    (net (code "32") (name "Battery") (class "Default")
      (node (ref "R31") (pin "2") (pinfunction "2_2") (pintype "passive"))
      (node (ref "RT1") (pin "1") (pinfunction "1_1") (pintype "passive"))
      (node (ref "VCC1") (pin "1") (pinfunction "VCC_1") (pintype "passive"))
    )
    (net (code "33") (name "Battery_out") (class "Default")
      (node (ref "C22") (pin "1") (pinfunction "1_1") (pintype "passive"))
      (node (ref "C23") (pin "1") (pinfunction "1_1") (pintype "passive"))
      (node (ref "C9") (pin "2") (pintype "passive"))
      (node (ref "E2") (pin "1") (pinfunction "1_1") (pintype "passive"))
      (node (ref "PD1") (pin "1") (pinfunction "A_1") (pintype "passive"))
      (node (ref "PD6") (pin "1") (pinfunction "A_1") (pintype "passive"))
      (node (ref "PU4") (pin "1") (pinfunction "VIN_1") (pintype "passive"))
      (node (ref "Q2") (pin "2") (pinfunction "D_2") (pintype "passive"))
      (node (ref "R33") (pin "1") (pinfunction "1_1") (pintype "passive"))
      (node (ref "R37") (pin "2") (pinfunction "2_2") (pintype "passive"))
      (node (ref "RL1") (pin "1") (pinfunction "1_1") (pintype "passive"))
      (node (ref "RT1") (pin "2") (pinfunction "2_2") (pintype "passive"))
    )
    (net (code "34") (name "Boost_OUT") (class "Default")
      (node (ref "BOOST_PM1") (pin "4") (pinfunction "VIN_4") (pintype "passive"))
      (node (ref "R36") (pin "2") (pinfunction "2_2") (pintype "passive"))
      (node (ref "RT3") (pin "1") (pinfunction "1_1") (pintype "passive"))
    )
    (net (code "35") (name "DGND") (class "Default")
      (node (ref "BOOST_PM1") (pin "2") (pinfunction "GND_2") (pintype "passive"))
      (node (ref "BOOST_PM1") (pin "3") (pinfunction "VING_3") (pintype "passive"))
    )
    (net (code "36") (name "GND") (class "Default")
      (node (ref "BOOST_PM1") (pin "5") (pinfunction "Hole_5") (pintype "passive"))
      (node (ref "BOOST_PM1") (pin "6") (pinfunction "Hole_6") (pintype "passive"))
      (node (ref "BOOST_PM1") (pin "7") (pinfunction "Hole_7") (pintype "passive"))
      (node (ref "BOOST_PM1") (pin "8") (pinfunction "Hole_8") (pintype "passive"))
      (node (ref "C1") (pin "2") (pinfunction "2_2") (pintype "passive"))
      (node (ref "C10") (pin "2") (pinfunction "2_2") (pintype "passive"))
      (node (ref "C11") (pin "2") (pinfunction "2_2") (pintype "passive"))
      (node (ref "C12") (pin "2") (pinfunction "2_2") (pintype "passive"))
      (node (ref "C13") (pin "1") (pinfunction "1_1") (pintype "passive"))
      (node (ref "C14") (pin "2") (pinfunction "2_2") (pintype "passive"))
      (node (ref "C15") (pin "2") (pinfunction "2_2") (pintype "passive"))
      (node (ref "C16") (pin "2") (pinfunction "2_2") (pintype "passive"))
      (node (ref "C17") (pin "1") (pinfunction "1_1") (pintype "passive"))
      (node (ref "C18") (pin "1") (pinfunction "1_1") (pintype "passive"))
      (node (ref "C19") (pin "1") (pinfunction "1_1") (pintype "passive"))
      (node (ref "C2") (pin "1") (pintype "passive"))
      (node (ref "C20") (pin "1") (pinfunction "1_1") (pintype "passive"))
      (node (ref "C21") (pin "2") (pinfunction "2_2") (pintype "passive"))
      (node (ref "C22") (pin "2") (pinfunction "2_2") (pintype "passive"))
      (node (ref "C23") (pin "2") (pinfunction "2_2") (pintype "passive"))
      (node (ref "C24") (pin "2") (pinfunction "2_2") (pintype "passive"))
      (node (ref "C25") (pin "2") (pinfunction "2_2") (pintype "passive"))
      (node (ref "C27") (pin "2") (pinfunction "2_2") (pintype "passive"))
      (node (ref "C28") (pin "2") (pinfunction "2_2") (pintype "passive"))
      (node (ref "C29") (pin "2") (pinfunction "2_2") (pintype "passive"))
      (node (ref "C3") (pin "2") (pinfunction "2_2") (pintype "passive"))
      (node (ref "C4") (pin "2") (pinfunction "2_2") (pintype "passive"))
      (node (ref "C5") (pin "2") (pinfunction "2_2") (pintype "passive"))
      (node (ref "C6") (pin "2") (pinfunction "2_2") (pintype "passive"))
      (node (ref "C7") (pin "1") (pintype "passive"))
      (node (ref "C8") (pin "2") (pinfunction "2_2") (pintype "passive"))
      (node (ref "C9") (pin "1") (pintype "passive"))
      (node (ref "CR1") (pin "2") (pinfunction "2_2") (pintype "passive"))
      (node (ref "CU1") (pin "9") (pinfunction "VSS_9") (pintype "passive"))
      (node (ref "Cap1") (pin "2") (pinfunction "GND_2") (pintype "passive"))
      (node (ref "E1") (pin "2") (pinfunction "2_2") (pintype "passive"))
      (node (ref "E2") (pin "2") (pinfunction "2_2") (pintype "passive"))
      (node (ref "L2") (pin "2") (pinfunction "K_2") (pintype "passive"))
      (node (ref "L3") (pin "2") (pinfunction "K_2") (pintype "passive"))
      (node (ref "L4") (pin "2") (pinfunction "K_2") (pintype "passive"))
      (node (ref "L5") (pin "2") (pinfunction "K_2") (pintype "passive"))
      (node (ref "L6") (pin "2") (pinfunction "K_2") (pintype "passive"))
      (node (ref "LED1") (pin "2") (pinfunction "K_2") (pintype "passive"))
      (node (ref "M1") (pin "2") (pinfunction "GND_2") (pintype "passive"))
      (node (ref "OP1") (pin "3") (pinfunction "E_3") (pintype "passive"))
      (node (ref "PU1") (pin "1") (pintype "passive"))
      (node (ref "PU2") (pin "1") (pintype "passive"))
      (node (ref "PU3") (pin "2") (pinfunction "GND_2") (pintype "passive"))
      (node (ref "PU4") (pin "4") (pinfunction "CS_4") (pintype "passive"))
      (node (ref "PU4") (pin "5") (pinfunction "GND_5") (pintype "passive"))
      (node (ref "PU4") (pin "6") (pinfunction "GND_6") (pintype "passive"))
      (node (ref "PU4") (pin "7") (pinfunction "GND_7") (pintype "passive"))
      (node (ref "PU4") (pin "8") (pinfunction "GND_8") (pintype "passive"))
      (node (ref "Q3") (pin "3") (pinfunction "S_3") (pintype "passive"))
      (node (ref "R10") (pin "2") (pinfunction "2_2") (pintype "passive"))
      (node (ref "R17") (pin "2") (pintype "passive"))
      (node (ref "R18") (pin "2") (pinfunction "2_2") (pintype "passive"))
      (node (ref "R2") (pin "1") (pinfunction "1_1") (pintype "passive"))
      (node (ref "R23") (pin "2") (pinfunction "2_2") (pintype "passive"))
      (node (ref "R24") (pin "2") (pinfunction "2_2") (pintype "passive"))
      (node (ref "R3") (pin "2") (pinfunction "2_2") (pintype "passive"))
      (node (ref "R7") (pin "2") (pinfunction "2_2") (pintype "passive"))
      (node (ref "S2") (pin "2") (pinfunction "2_2") (pintype "passive"))
      (node (ref "SS1") (pin "1") (pinfunction "A_1") (pintype "passive"))
      (node (ref "U1") (pin "2") (pinfunction "GND_2") (pintype "passive"))
      (node (ref "U2") (pin "2") (pinfunction "GXD_2") (pintype "passive"))
      (node (ref "U2") (pin "8") (pinfunction "Rs_8") (pintype "passive"))
      (node (ref "U3") (pin "23") (pinfunction "VSS_1_23") (pintype "passive"))
      (node (ref "U3") (pin "35") (pinfunction "VSS_2_35") (pintype "passive"))
      (node (ref "U3") (pin "47") (pinfunction "VSS_3_47") (pintype "passive"))
      (node (ref "VCC1") (pin "2") (pinfunction "GND_2") (pintype "passive"))
    )
    (net (code "37") (name "Moter") (class "Default")
      (node (ref "M1") (pin "1") (pinfunction "VCC_1") (pintype "passive"))
      (node (ref "PD1") (pin "2") (pinfunction "K_2") (pintype "passive"))
      (node (ref "PD2") (pin "2") (pinfunction "K_2") (pintype "passive"))
      (node (ref "PD4") (pin "2") (pinfunction "K_2") (pintype "passive"))
      (node (ref "PD6") (pin "2") (pinfunction "K_2") (pintype "passive"))
    )
    (net (code "38") (name "Net-(BOOST_PM1-VOUT)") (class "Default")
      (node (ref "BOOST_PM1") (pin "1") (pinfunction "VOUT_1") (pintype "passive"))
      (node (ref "Q1") (pin "2") (pinfunction "D_2") (pintype "passive"))
    )
    (net (code "39") (name "Net-(C13-Pad2)") (class "Default")
      (node (ref "C13") (pin "2") (pinfunction "2_2") (pintype "passive"))
      (node (ref "C14") (pin "1") (pinfunction "1_1") (pintype "passive"))
      (node (ref "R4") (pin "2") (pinfunction "2_2") (pintype "passive"))
      (node (ref "R5") (pin "1") (pinfunction "1_1") (pintype "passive"))
    )
    (net (code "40") (name "Net-(CU1-HB)") (class "Default")
      (node (ref "C26") (pin "1") (pinfunction "1_1") (pintype "passive"))
      (node (ref "CU1") (pin "2") (pinfunction "HB_2") (pintype "passive"))
      (node (ref "D2") (pin "2") (pinfunction "2_2") (pintype "passive"))
    )
    (net (code "41") (name "Net-(CU1-HO)") (class "Default")
      (node (ref "CU1") (pin "3") (pinfunction "HO_3") (pintype "passive"))
      (node (ref "D3") (pin "2") (pinfunction "2_2") (pintype "passive"))
      (node (ref "R19") (pin "1") (pinfunction "1_1") (pintype "passive"))
    )
    (net (code "42") (name "Net-(CU1-HS)") (class "Default")
      (node (ref "C26") (pin "2") (pinfunction "2_2") (pintype "passive"))
      (node (ref "CU1") (pin "4") (pinfunction "HS_4") (pintype "passive"))
      (node (ref "L7") (pin "1") (pinfunction "1_1") (pintype "passive"))
      (node (ref "Q2") (pin "3") (pinfunction "S_3") (pintype "passive"))
      (node (ref "Q3") (pin "2") (pinfunction "D_2") (pintype "passive"))
      (node (ref "R20") (pin "2") (pinfunction "2_2") (pintype "passive"))
    )
    (net (code "43") (name "Net-(CU1-LO)") (class "Default")
      (node (ref "CU1") (pin "10") (pinfunction "LO_10") (pintype "passive"))
      (node (ref "D4") (pin "2") (pinfunction "K_2") (pintype "passive"))
      (node (ref "R22") (pin "1") (pinfunction "1_1") (pintype "passive"))
    )
    (net (code "44") (name "Net-(CU1-RDT)") (class "Default")
      (node (ref "CU1") (pin "6") (pinfunction "RDT_6") (pintype "passive"))
      (node (ref "R23") (pin "1") (pinfunction "1_1") (pintype "passive"))
    )
    (net (code "45") (name "Net-(D1-K)") (class "Default")
      (node (ref "C21") (pin "1") (pinfunction "1_1") (pintype "passive"))
      (node (ref "D1") (pin "2") (pinfunction "K_2") (pintype "passive"))
      (node (ref "U3") (pin "1") (pinfunction "VBAT_1") (pintype "passive"))
    )
    (net (code "46") (name "Net-(D4-A)") (class "Default")
      (node (ref "D4") (pin "1") (pinfunction "A_1") (pintype "passive"))
      (node (ref "Q3") (pin "1") (pinfunction "G_1") (pintype "passive"))
      (node (ref "R22") (pin "2") (pinfunction "2_2") (pintype "passive"))
      (node (ref "R24") (pin "1") (pinfunction "1_1") (pintype "passive"))
    )
    (net (code "47") (name "Net-(L2-A)") (class "Default")
      (node (ref "L2") (pin "1") (pinfunction "A_1") (pintype "passive"))
      (node (ref "R8") (pin "2") (pinfunction "2_2") (pintype "passive"))
    )
    (net (code "48") (name "Net-(L3-A)") (class "Default")
      (node (ref "L3") (pin "1") (pinfunction "A_1") (pintype "passive"))
      (node (ref "R9") (pin "1") (pinfunction "1_1") (pintype "passive"))
    )
    (net (code "49") (name "Net-(L4-A)") (class "Default")
      (node (ref "L4") (pin "1") (pinfunction "A_1") (pintype "passive"))
      (node (ref "R11") (pin "1") (pinfunction "1_1") (pintype "passive"))
    )
    (net (code "50") (name "Net-(L5-A)") (class "Default")
      (node (ref "L5") (pin "1") (pinfunction "A_1") (pintype "passive"))
      (node (ref "R12") (pin "1") (pinfunction "1_1") (pintype "passive"))
    )
    (net (code "51") (name "Net-(L6-A)") (class "Default")
      (node (ref "L6") (pin "1") (pinfunction "A_1") (pintype "passive"))
      (node (ref "R13") (pin "1") (pinfunction "1_1") (pintype "passive"))
    )
    (net (code "52") (name "Net-(LED1-A)") (class "Default")
      (node (ref "LED1") (pin "1") (pinfunction "A_1") (pintype "passive"))
      (node (ref "R21") (pin "1") (pinfunction "1_1") (pintype "passive"))
    )
    (net (code "53") (name "Net-(OP1-C)") (class "Default")
      (node (ref "OP1") (pin "4") (pinfunction "C_4") (pintype "passive"))
      (node (ref "Q1") (pin "1") (pinfunction "G_1") (pintype "passive"))
      (node (ref "RPL1") (pin "2") (pinfunction "2_2") (pintype "passive"))
    )
    (net (code "54") (name "Net-(OP1-K)") (class "Default")
      (node (ref "OP1") (pin "2") (pinfunction "K_2") (pintype "passive"))
      (node (ref "R18") (pin "1") (pinfunction "1_1") (pintype "passive"))
    )
    (net (code "55") (name "Net-(PU3-VIN)") (class "Default")
      (node (ref "C7") (pin "2") (pintype "passive"))
      (node (ref "PU3") (pin "3") (pinfunction "VIN_3") (pintype "passive"))
      (node (ref "RL1") (pin "2") (pinfunction "2_2") (pintype "passive"))
    )
    (net (code "56") (name "Net-(PU4-FB)") (class "Default")
      (node (ref "PU4") (pin "3") (pinfunction "FB_3") (pintype "passive"))
      (node (ref "R1") (pin "1") (pinfunction "1_1") (pintype "passive"))
      (node (ref "R2") (pin "2") (pinfunction "2_2") (pintype "passive"))
    )
    (net (code "57") (name "Net-(PU4-SW)") (class "Default")
      (node (ref "L1") (pin "1") (pinfunction "1_1") (pintype "passive"))
      (node (ref "PU4") (pin "2") (pinfunction "SW_2") (pintype "passive"))
      (node (ref "SS1") (pin "2") (pinfunction "K_2") (pintype "passive"))
    )
    (net (code "58") (name "Net-(Q2-G)") (class "Default")
      (node (ref "D3") (pin "1") (pinfunction "1_1") (pintype "passive"))
      (node (ref "Q2") (pin "1") (pinfunction "G_1") (pintype "passive"))
      (node (ref "R19") (pin "2") (pinfunction "2_2") (pintype "passive"))
      (node (ref "R20") (pin "1") (pinfunction "1_1") (pintype "passive"))
    )
    (net (code "59") (name "Net-(U3-BOOT0)") (class "Default")
      (node (ref "R17") (pin "1") (pintype "passive"))
      (node (ref "U3") (pin "44") (pinfunction "BOOT0_44") (pintype "passive"))
    )
    (net (code "60") (name "Net-(U3-NRST)") (class "Default")
      (node (ref "CR1") (pin "1") (pinfunction "1_1") (pintype "passive"))
      (node (ref "R16") (pin "2") (pintype "passive"))
      (node (ref "U3") (pin "7") (pinfunction "NRST_7") (pintype "passive"))
    )
    (net (code "61") (name "Net-(U3-PD0{slash}OSC_IN)") (class "Default")
      (node (ref "C20") (pin "2") (pinfunction "2_2") (pintype "passive"))
      (node (ref "U3") (pin "5") (pinfunction "PD0/OSC_IN_5") (pintype "passive"))
      (node (ref "Y1") (pin "2") (pinfunction "OSC2_2") (pintype "passive"))
    )
    (net (code "62") (name "Net-(U3-PDI{slash}OSC_OUT)") (class "Default")
      (node (ref "C19") (pin "2") (pinfunction "2_2") (pintype "passive"))
      (node (ref "U3") (pin "6") (pinfunction "PDI/OSC_OUT_6") (pintype "passive"))
      (node (ref "Y1") (pin "1") (pinfunction "OSC1_1") (pintype "passive"))
    )
    (net (code "63") (name "Net-(U4-IN+)") (class "Default")
      (node (ref "C33") (pin "1") (pinfunction "1_1") (pintype "passive"))
      (node (ref "R31") (pin "1") (pinfunction "1_1") (pintype "passive"))
      (node (ref "U4") (pin "10") (pinfunction "IN+_10") (pintype "passive"))
    )
    (net (code "64") (name "Net-(U4-IN-)") (class "Default")
      (node (ref "C33") (pin "2") (pinfunction "2_2") (pintype "passive"))
      (node (ref "R37") (pin "1") (pinfunction "1_1") (pintype "passive"))
      (node (ref "U4") (pin "9") (pinfunction "IN-_9") (pintype "passive"))
    )
    (net (code "65") (name "Net-(U5-IN+)") (class "Default")
      (node (ref "C34") (pin "1") (pinfunction "1_1") (pintype "passive"))
      (node (ref "R34") (pin "1") (pinfunction "1_1") (pintype "passive"))
      (node (ref "U5") (pin "10") (pinfunction "IN+_10") (pintype "passive"))
    )
    (net (code "66") (name "Net-(U5-IN-)") (class "Default")
      (node (ref "C34") (pin "2") (pinfunction "2_2") (pintype "passive"))
      (node (ref "R38") (pin "1") (pinfunction "1_1") (pintype "passive"))
      (node (ref "U5") (pin "9") (pinfunction "IN-_9") (pintype "passive"))
    )
    (net (code "67") (name "Net-(U6-A0)") (class "Default")
      (node (ref "R40") (pin "1") (pinfunction "1_1") (pintype "passive"))
      (node (ref "U6") (pin "2") (pinfunction "A0_2") (pintype "passive"))
    )
    (net (code "68") (name "Net-(U6-IN+)") (class "Default")
      (node (ref "C35") (pin "1") (pinfunction "1_1") (pintype "passive"))
      (node (ref "R36") (pin "1") (pinfunction "1_1") (pintype "passive"))
      (node (ref "U6") (pin "10") (pinfunction "IN+_10") (pintype "passive"))
    )
    (net (code "69") (name "Net-(U6-IN-)") (class "Default")
      (node (ref "C35") (pin "2") (pinfunction "2_2") (pintype "passive"))
      (node (ref "R39") (pin "1") (pinfunction "1_1") (pintype "passive"))
      (node (ref "U6") (pin "9") (pinfunction "IN-_9") (pintype "passive"))
    )
    (net (code "70") (name "Power_Cap") (class "Default")
      (node (ref "Cap1") (pin "1") (pinfunction "VCC_1") (pintype "passive"))
      (node (ref "Q1") (pin "3") (pinfunction "S_3") (pintype "passive"))
      (node (ref "R32") (pin "1") (pinfunction "1_1") (pintype "passive"))
      (node (ref "R38") (pin "2") (pinfunction "2_2") (pintype "passive"))
      (node (ref "RPL1") (pin "1") (pinfunction "1_1") (pintype "passive"))
      (node (ref "RT2") (pin "2") (pinfunction "2_2") (pintype "passive"))
    )
    (net (code "71") (name "Power_Charge") (class "Default")
      (node (ref "C27") (pin "1") (pinfunction "1_1") (pintype "passive"))
      (node (ref "C28") (pin "1") (pinfunction "1_1") (pintype "passive"))
      (node (ref "C29") (pin "1") (pinfunction "1_1") (pintype "passive"))
      (node (ref "L7") (pin "2") (pinfunction "2_2") (pintype "passive"))
      (node (ref "PD3") (pin "1") (pinfunction "A_1") (pintype "passive"))
      (node (ref "PD5") (pin "1") (pinfunction "A_1") (pintype "passive"))
      (node (ref "R21") (pin "2") (pinfunction "2_2") (pintype "passive"))
    )
    (net (code "72") (name "Power_Charge_OUT") (class "Default")
      (node (ref "PD3") (pin "2") (pinfunction "K_2") (pintype "passive"))
      (node (ref "PD5") (pin "2") (pinfunction "K_2") (pintype "passive"))
      (node (ref "R34") (pin "2") (pinfunction "2_2") (pintype "passive"))
      (node (ref "RT2") (pin "1") (pinfunction "1_1") (pintype "passive"))
    )
    (net (code "73") (name "SUPERCAP_OUT") (class "Default")
      (node (ref "PD2") (pin "1") (pinfunction "A_1") (pintype "passive"))
      (node (ref "PD4") (pin "1") (pinfunction "A_1") (pintype "passive"))
      (node (ref "R35") (pin "1") (pinfunction "1_1") (pintype "passive"))
      (node (ref "R39") (pin "2") (pinfunction "2_2") (pintype "passive"))
      (node (ref "RT3") (pin "2") (pinfunction "2_2") (pintype "passive"))
    )
    (net (code "74") (name "VDDA") (class "Default")
      (node (ref "C15") (pin "1") (pinfunction "1_1") (pintype "passive"))
      (node (ref "C16") (pin "1") (pinfunction "1_1") (pintype "passive"))
      (node (ref "R5") (pin "2") (pinfunction "2_2") (pintype "passive"))
      (node (ref "U3") (pin "9") (pinfunction "VDDA_9") (pintype "passive"))
    )
    (net (code "75") (name "VSSA") (class "Default")
      (node (ref "R7") (pin "1") (pinfunction "1_1") (pintype "passive"))
      (node (ref "U3") (pin "8") (pinfunction "VSSA_8") (pintype "passive"))
    )
    (net (code "76") (name "unconnected-(CU1-NC-Pad5)") (class "Default")
      (node (ref "CU1") (pin "5") (pinfunction "NC_5") (pintype "passive"))
    )
    (net (code "77") (name "unconnected-(U2-Vref-Pad5)") (class "Default")
      (node (ref "U2") (pin "5") (pinfunction "Vref_5") (pintype "passive"))
    )
    (net (code "78") (name "unconnected-(U3-PA1{slash}USART2_RTS{slash}ADC12_0IN1{slash}TIM2_CH2-Pad11)") (class "Default")
      (node (ref "U3") (pin "11") (pinfunction "PA1/USART2_RTS/ADC12_0IN1/TIM2_CH2_11") (pintype "passive"))
    )
    (net (code "79") (name "unconnected-(U3-PA7{slash}SPI1_MOSI{slash}ADC12_IN7{slash}TIM3_CH2{slash}TIM1_CH1N-Pad17)") (class "Default")
      (node (ref "U3") (pin "17") (pinfunction "PA7/SPI1_MOSI/ADC12_IN7/TIM3_CH2/TIM1_CH1N_17") (pintype "passive"))
    )
    (net (code "80") (name "unconnected-(U3-PA8{slash}USART1_CK{slash}TIM1_CH1{slash}MCO-Pad29)") (class "Default")
      (node (ref "U3") (pin "29") (pinfunction "PA8/USART1_CK/TIM1_CH1/MCO_29") (pintype "passive"))
    )
    (net (code "81") (name "unconnected-(U3-PA9{slash}USART1_TX{slash}TIM1_CH2-Pad30)") (class "Default")
      (node (ref "U3") (pin "30") (pinfunction "PA9/USART1_TX/TIM1_CH2_30") (pintype "passive"))
    )
    (net (code "82") (name "unconnected-(U3-PA10{slash}USART1_RX{slash}TIM1_CH3-Pad31)") (class "Default")
      (node (ref "U3") (pin "31") (pinfunction "PA10/USART1_RX/TIM1_CH3_31") (pintype "passive"))
    )
    (net (code "83") (name "unconnected-(U3-PA11{slash}USART1_CTS{slash}CANRX{slash}USBDM{slash}TIM1_CH4-Pad32)") (class "Default")
      (node (ref "U3") (pin "32") (pinfunction "PA11/USART1_CTS/CANRX/USBDM/TIM1_CH4_32") (pintype "passive"))
    )
    (net (code "84") (name "unconnected-(U3-PA12{slash}USART1_RTS{slash}CANTX{slash}USBDP{slash}TIM1_ETR-Pad33)") (class "Default")
      (node (ref "U3") (pin "33") (pinfunction "PA12/USART1_RTS/CANTX/USBDP/TIM1_ETR_33") (pintype "passive"))
    )
    (net (code "85") (name "unconnected-(U3-PAO{slash}WKUP{slash}USART2_CTS{slash}ADC12_IN0{slash}TIM2_CH1_ETR-Pad10)") (class "Default")
      (node (ref "U3") (pin "10") (pinfunction "PAO/WKUP/USART2_CTS/ADC12_IN0/TIM2_CH1_ETR_10") (pintype "passive"))
    )
    (net (code "86") (name "unconnected-(U3-PB0{slash}ADC12_IN8{slash}TIM3_CH3{slash}TIM1_CH2N-Pad18)") (class "Default")
      (node (ref "U3") (pin "18") (pinfunction "PB0/ADC12_IN8/TIM3_CH3/TIM1_CH2N_18") (pintype "passive"))
    )
    (net (code "87") (name "unconnected-(U3-PB1{slash}ADC12_IN9{slash}TIM3_CH4{slash}TIM1_CH3N-Pad19)") (class "Default")
      (node (ref "U3") (pin "19") (pinfunction "PB1/ADC12_IN9/TIM3_CH4/TIM1_CH3N_19") (pintype "passive"))
    )
    (net (code "88") (name "unconnected-(U3-PB2{slash}BOOT1-Pad20)") (class "Default")
      (node (ref "U3") (pin "20") (pinfunction "PB2/BOOT1_20") (pintype "passive"))
    )
    (net (code "89") (name "unconnected-(U3-PB5{slash}I2C1_SMBAI{slash}TIM3_CH2{slash}SPI1_MOSI-Pad41)") (class "Default")
      (node (ref "U3") (pin "41") (pinfunction "PB5/I2C1_SMBAI/TIM3_CH2/SPI1_MOSI_41") (pintype "passive"))
    )
    (net (code "90") (name "unconnected-(U3-PB12{slash}SPI2_NSS{slash}I2C2_SMBAI{slash}USART3_CK{slash}TIM1_BKIN-Pad25)") (class "Default")
      (node (ref "U3") (pin "25") (pinfunction "PB12/SPI2_NSS/I2C2_SMBAI/USART3_CK/TIM1_BKIN_25") (pintype "passive"))
    )
    (net (code "91") (name "unconnected-(U3-PB13{slash}SPI2_SCK{slash}USART3_CTS{slash}TIM1_CH1N-Pad26)") (class "Default")
      (node (ref "U3") (pin "26") (pinfunction "PB13/SPI2_SCK/USART3_CTS/TIM1_CH1N_26") (pintype "passive"))
    )
    (net (code "92") (name "unconnected-(U3-PB14{slash}SPI2_MISO{slash}USART3_RTS{slash}TIM1_CH2N-Pad27)") (class "Default")
      (node (ref "U3") (pin "27") (pinfunction "PB14/SPI2_MISO/USART3_RTS/TIM1_CH2N_27") (pintype "passive"))
    )
    (net (code "93") (name "unconnected-(U3-PB15{slash}SPI2_MOSI{slash}TIM1_CH3N-Pad28)") (class "Default")
      (node (ref "U3") (pin "28") (pinfunction "PB15/SPI2_MOSI/TIM1_CH3N_28") (pintype "passive"))
    )
    (net (code "94") (name "unconnected-(U3-PC13{slash}TAMPER-RTC-Pad2)") (class "Default")
      (node (ref "U3") (pin "2") (pinfunction "PC13/TAMPER-RTC_2") (pintype "passive"))
    )
    (net (code "95") (name "unconnected-(U3-PC14{slash}OSC32_IN-Pad3)") (class "Default")
      (node (ref "U3") (pin "3") (pinfunction "PC14/OSC32_IN_3") (pintype "passive"))
    )
    (net (code "96") (name "unconnected-(U3-PC15{slash}OSC32_OUT-Pad4)") (class "Default")
      (node (ref "U3") (pin "4") (pinfunction "PC15/OSC32_OUT_4") (pintype "passive"))
    )
    (net (code "97") (name "unconnected-(U4-Alert-Pad3)") (class "Default")
      (node (ref "U4") (pin "3") (pinfunction "Alert_3") (pintype "passive"))
    )
    (net (code "98") (name "unconnected-(U5-Alert-Pad3)") (class "Default")
      (node (ref "U5") (pin "3") (pinfunction "Alert_3") (pintype "passive"))
    )
    (net (code "99") (name "unconnected-(U6-Alert-Pad3)") (class "Default")
      (node (ref "U6") (pin "3") (pinfunction "Alert_3") (pintype "passive"))
    )
  )
)
